# LPC55S69_MINI.net
KiCad netlist of a schematic drawn in Altium Designer
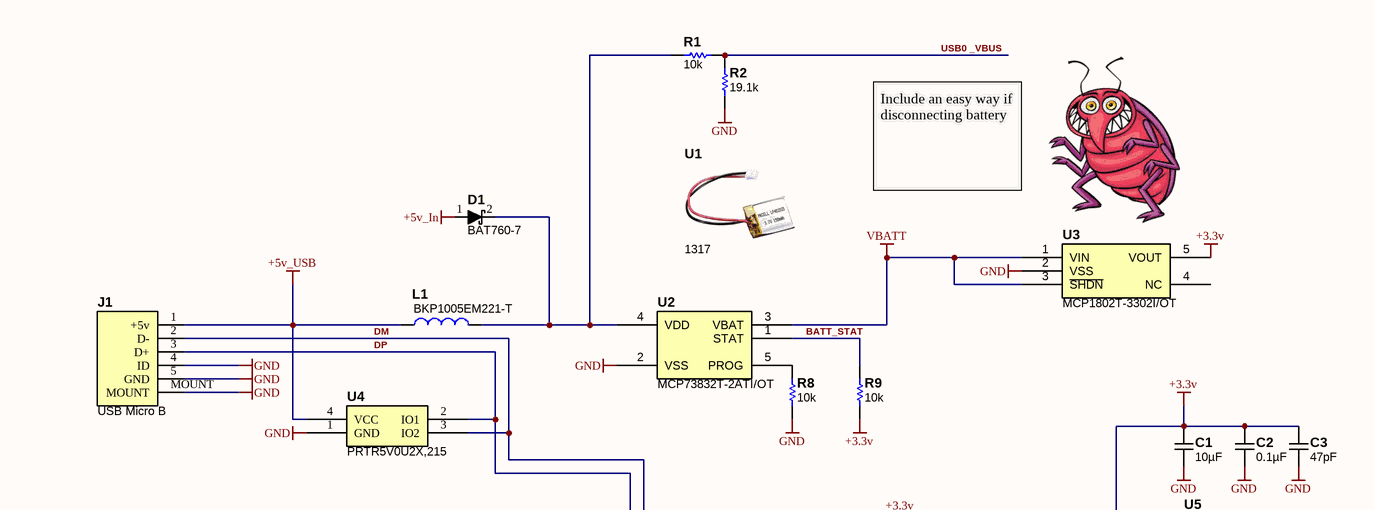
[diagram p0: LPC55S69_MINI.SchDoc, top left]
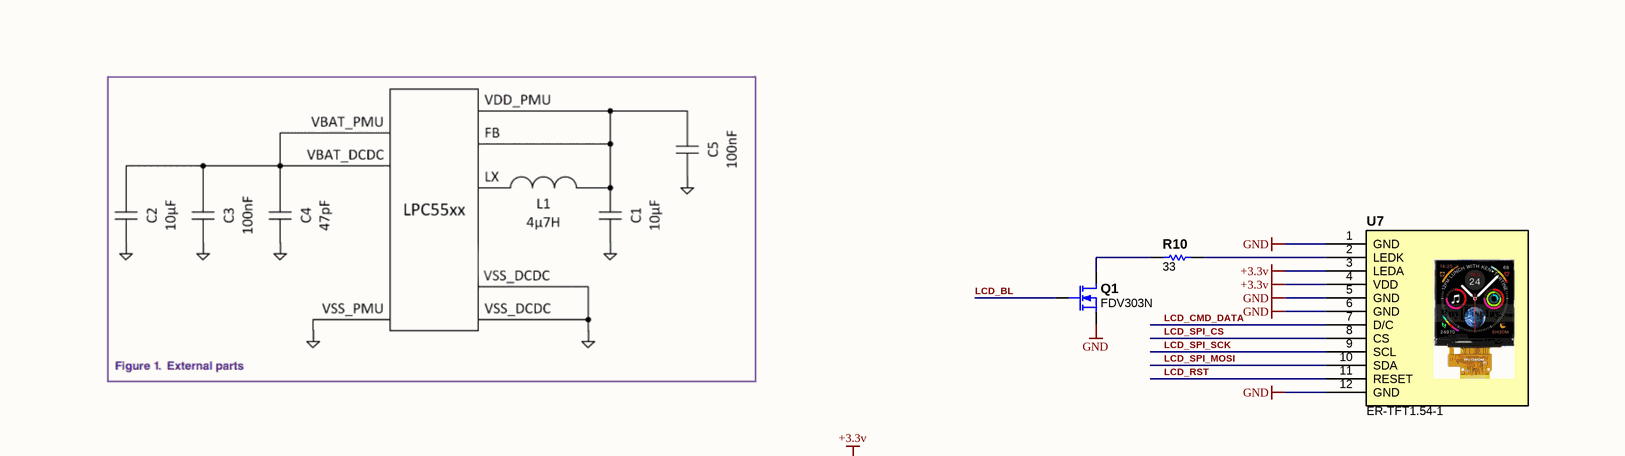
[diagram p1: LPC55S69_MINI.SchDoc, top right]
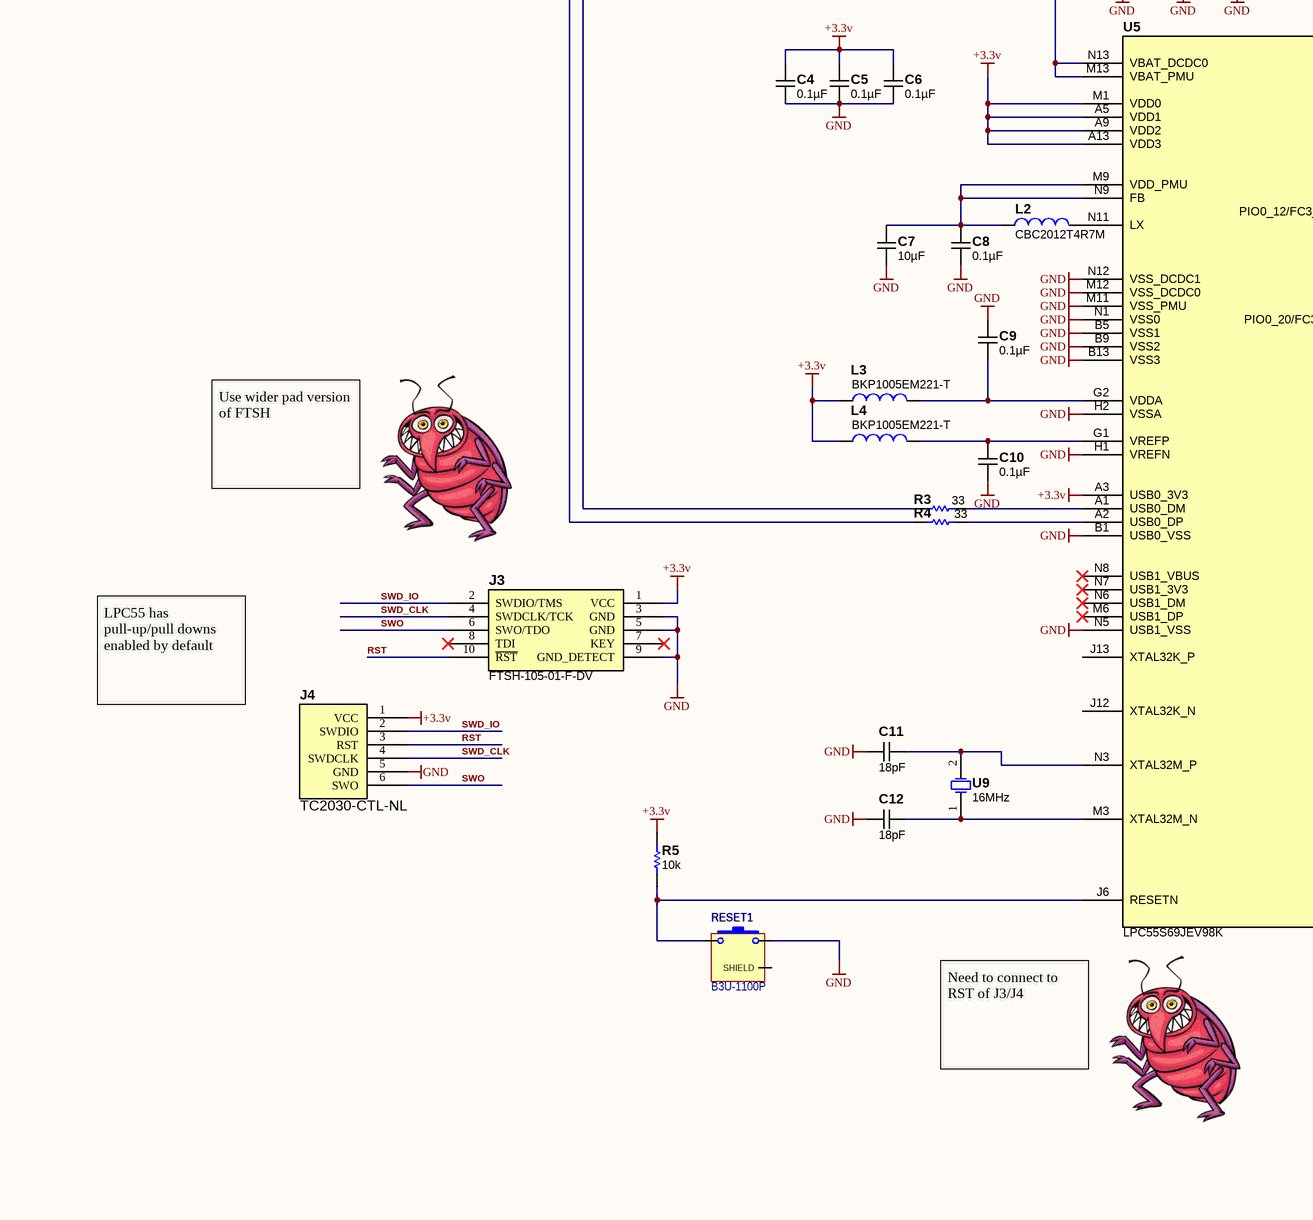
[diagram p2: LPC55S69_MINI.SchDoc, bottom left]
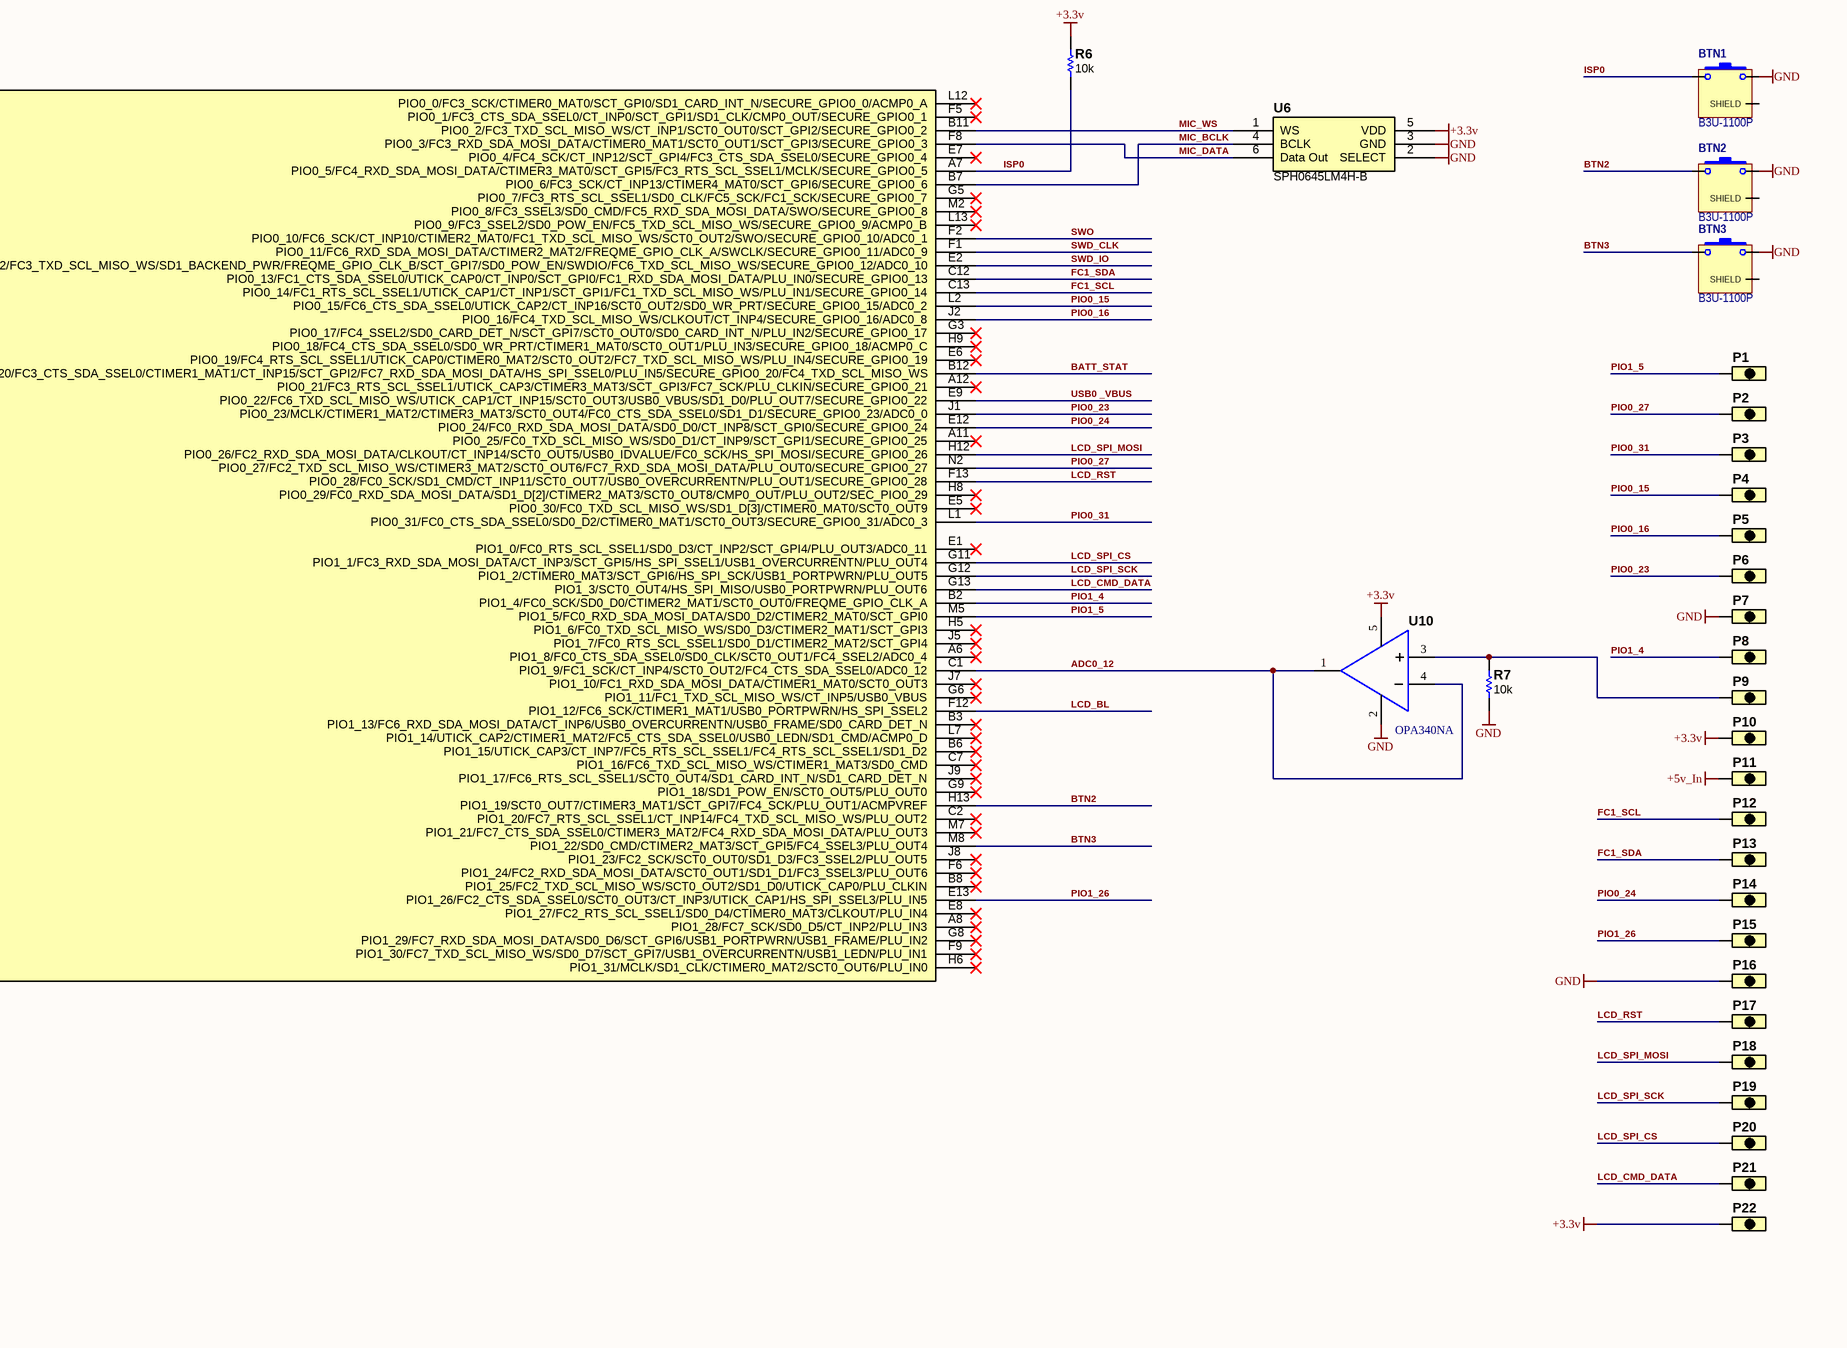
[diagram p3: LPC55S69_MINI.SchDoc, bottom right]

(export (version "E")
  (design (tool "Eeschema 10.0.6"))
  (components
    (comp (ref "BTN1")
      (value "B3U-1100P")
      (footprint "OMRON_B3U-1100P")
      (description "SWITCH TACTILE SPST-NO 0.05A 12V")
      (fields (field (name "MANUFACTURER") "Omron Electronics Inc-EMC Div"))
      (libsource (lib "Switches-N") (part "B3U-1100P"))
    )
    (comp (ref "BTN2")
      (value "B3U-1100P")
      (footprint "OMRON_B3U-1100P")
      (description "SWITCH TACTILE SPST-NO 0.05A 12V")
      (fields (field (name "MANUFACTURER") "Omron Electronics Inc-EMC Div"))
      (libsource (lib "Switches-N") (part "B3U-1100P"))
    )
    (comp (ref "BTN3")
      (value "B3U-1100P")
      (footprint "OMRON_B3U-1100P")
      (description "SWITCH TACTILE SPST-NO 0.05A 12V")
      (fields (field (name "MANUFACTURER") "Omron Electronics Inc-EMC Div"))
      (libsource (lib "Switches-N") (part "B3U-1100P"))
    )
    (comp (ref "C1")
      (value "10µF")
      (footprint "C0805_1.45MM_MD")
      (description "CAP CER 10UF 6.3V X7R 0805")
      (fields
        (field (name "MANUFACTURER PART NUMBER") "CGA4J1X7R0J106K125AC")
        (field (name "MANUFACTURER") "TDK Corporation")
      )
      (libsource (lib "Capacitors - TDK- AEC-Q200") (part "C_2P_NP"))
    )
    (comp (ref "C2")
      (value "0.1µF")
      (footprint "C0402_0.55MM_MD")
      (description "CAP CER 0.1UF 16V X7R 0402")
      (fields
        (field (name "MANUFACTURER PART NUMBER") "CGA2B1X7R1C104K050BC")
        (field (name "MANUFACTURER") "TDK Corporation")
      )
      (libsource (lib "Capacitors - TDK- AEC-Q200") (part "C_2P_NP"))
    )
    (comp (ref "C3")
      (value "47pF")
      (footprint "C0402_0.55MM_MD")
      (description "CAP CER 47PF 50V C0G 0402")
      (fields
        (field (name "MANUFACTURER PART NUMBER") "CGA2B2C0G1H470J050BA")
        (field (name "MANUFACTURER") "TDK Corporation")
      )
      (libsource (lib "Capacitors - TDK- AEC-Q200") (part "C_2P_NP"))
    )
    (comp (ref "C4")
      (value "0.1µF")
      (footprint "C0402_0.55MM_MD")
      (description "CAP CER 0.1UF 16V X7R 0402")
      (fields
        (field (name "MANUFACTURER PART NUMBER") "CGA2B1X7R1C104K050BC")
        (field (name "MANUFACTURER") "TDK Corporation")
      )
      (libsource (lib "Capacitors - TDK- AEC-Q200") (part "C_2P_NP"))
    )
    (comp (ref "C5")
      (value "0.1µF")
      (footprint "C0402_0.55MM_MD")
      (description "CAP CER 0.1UF 16V X7R 0402")
      (fields
        (field (name "MANUFACTURER PART NUMBER") "CGA2B1X7R1C104K050BC")
        (field (name "MANUFACTURER") "TDK Corporation")
      )
      (libsource (lib "Capacitors - TDK- AEC-Q200") (part "C_2P_NP"))
    )
    (comp (ref "C6")
      (value "0.1µF")
      (footprint "C0402_0.55MM_MD")
      (description "CAP CER 0.1UF 16V X7R 0402")
      (fields
        (field (name "MANUFACTURER PART NUMBER") "CGA2B1X7R1C104K050BC")
        (field (name "MANUFACTURER") "TDK Corporation")
      )
      (libsource (lib "Capacitors - TDK- AEC-Q200") (part "C_2P_NP"))
    )
    (comp (ref "C7")
      (value "10µF")
      (footprint "C0805_1.45MM_MD")
      (description "CAP CER 10UF 6.3V X7R 0805")
      (fields
        (field (name "MANUFACTURER PART NUMBER") "CGA4J1X7R0J106K125AC")
        (field (name "MANUFACTURER") "TDK Corporation")
      )
      (libsource (lib "Capacitors - TDK- AEC-Q200") (part "C_2P_NP"))
    )
    (comp (ref "C8")
      (value "0.1µF")
      (footprint "C0402_0.55MM_MD")
      (description "CAP CER 0.1UF 16V X7R 0402")
      (fields
        (field (name "MANUFACTURER PART NUMBER") "CGA2B1X7R1C104K050BC")
        (field (name "MANUFACTURER") "TDK Corporation")
      )
      (libsource (lib "Capacitors - TDK- AEC-Q200") (part "C_2P_NP"))
    )
    (comp (ref "C9")
      (value "0.1µF")
      (footprint "C0402_0.55MM_MD")
      (description "CAP CER 0.1UF 16V X7R 0402")
      (fields
        (field (name "MANUFACTURER PART NUMBER") "CGA2B1X7R1C104K050BC")
        (field (name "MANUFACTURER") "TDK Corporation")
      )
      (libsource (lib "Capacitors - TDK- AEC-Q200") (part "C_2P_NP"))
    )
    (comp (ref "C10")
      (value "0.1µF")
      (footprint "C0402_0.55MM_MD")
      (description "CAP CER 0.1UF 16V X7R 0402")
      (fields
        (field (name "MANUFACTURER PART NUMBER") "CGA2B1X7R1C104K050BC")
        (field (name "MANUFACTURER") "TDK Corporation")
      )
      (libsource (lib "Capacitors - TDK- AEC-Q200") (part "C_2P_NP"))
    )
    (comp (ref "C11")
      (value "18pF")
      (footprint "C0402_0.55MM_MD")
      (description "CAP CER 18PF 50V C0G 0402")
      (fields
        (field (name "MANUFACTURER PART NUMBER") "CGA2B2C0G1H180J050BA")
        (field (name "MANUFACTURER") "TDK Corporation")
      )
      (libsource (lib "Capacitors - TDK- AEC-Q200") (part "C_2P_NP"))
    )
    (comp (ref "C12")
      (value "18pF")
      (footprint "C0402_0.55MM_MD")
      (description "CAP CER 18PF 50V C0G 0402")
      (fields
        (field (name "MANUFACTURER PART NUMBER") "CGA2B2C0G1H180J050BA")
        (field (name "MANUFACTURER") "TDK Corporation")
      )
      (libsource (lib "Capacitors - TDK- AEC-Q200") (part "C_2P_NP"))
    )
    (comp (ref "D1")
      (value "BAT760-7")
      (footprint "D_SOD-323_P")
      (description "DIODE SCHOTTKY 30V 1A SOD323")
      (fields (field (name "MANUFACTURER") "Diodes Inc"))
      (libsource (lib "Diodes") (part "DS_1A_2C"))
    )
    (comp (ref "J1")
      (value "USB Micro B")
      (footprint "10103594-0001LF")
      (description "CONN RCPT STD MICRO USB TYPE B")
      (fields (field (name "MANUFACTURER") "FCI") (field (name "MANUFACTURER PART NUMBER") "10103594-0001LF"))
      (libsource (lib "eConnector_USB") (part "10103594-0001LF"))
    )
    (comp (ref "J3")
      (value "FTSH-105-01-F-DV")
      (footprint "FTSH-105-04-F-DV - HD - NO_STEP")
      (description "SAMTEC - FTSH-105-01-F-DV - .050 X .050")
      (fields (field (name "MANUFACTURER") "SAMTEC"))
      (libsource (lib "eConnector") (part "CORTEX-DEBUG"))
    )
    (comp (ref "J4")
      (value "TC2030‐CTL‐NL")
      (footprint "TC2030 NO LATCH")
      (description "Tag Connect Pads - No latching Clips - ARM")
      (libsource (lib "eConnector") (part "TC2030‐CTL‐NL"))
    )
    (comp (ref "L1")
      (value "BKP1005EM221-T")
      (footprint "C0402_HD")
      (description "FERRITE BEAD 220 OHM 0402 1LN")
      (fields (field (name "MANUFACTURER") "Taiyo Yuden"))
      (libsource (lib "eInductor") (part "BKP1005EM221-T"))
    )
    (comp (ref "L2")
      (value "CBC2012T4R7M")
      (footprint "C0805_1.45MM_MD")
      (description "FIXED IND 4.7UH 520MA 650 MOHM")
      (fields (field (name "MANUFACTURER") "Taiyo Yuden") (field (name "TOLERANCE") "20%"))
      (libsource (lib "eInductor") (part "CBC2012T4R7M"))
    )
    (comp (ref "L3")
      (value "BKP1005EM221-T")
      (footprint "C0402_HD")
      (description "FERRITE BEAD 220 OHM 0402 1LN")
      (fields (field (name "MANUFACTURER") "Taiyo Yuden"))
      (libsource (lib "eInductor") (part "BKP1005EM221-T"))
    )
    (comp (ref "L4")
      (value "BKP1005EM221-T")
      (footprint "C0402_HD")
      (description "FERRITE BEAD 220 OHM 0402 1LN")
      (fields (field (name "MANUFACTURER") "Taiyo Yuden"))
      (libsource (lib "eInductor") (part "BKP1005EM221-T"))
    )
    (comp (ref "P1")
      (value "~")
      (footprint "CASTELLATED")
      (libsource (lib "eConnector") (part "CASTELLATED"))
    )
    (comp (ref "P2")
      (value "~")
      (footprint "CASTELLATED")
      (libsource (lib "eConnector") (part "CASTELLATED"))
    )
    (comp (ref "P3")
      (value "~")
      (footprint "CASTELLATED")
      (libsource (lib "eConnector") (part "CASTELLATED"))
    )
    (comp (ref "P4")
      (value "~")
      (footprint "CASTELLATED")
      (libsource (lib "eConnector") (part "CASTELLATED"))
    )
    (comp (ref "P5")
      (value "~")
      (footprint "CASTELLATED")
      (libsource (lib "eConnector") (part "CASTELLATED"))
    )
    (comp (ref "P6")
      (value "~")
      (footprint "CASTELLATED")
      (libsource (lib "eConnector") (part "CASTELLATED"))
    )
    (comp (ref "P7")
      (value "~")
      (footprint "CASTELLATED")
      (libsource (lib "eConnector") (part "CASTELLATED"))
    )
    (comp (ref "P8")
      (value "~")
      (footprint "CASTELLATED")
      (libsource (lib "eConnector") (part "CASTELLATED"))
    )
    (comp (ref "P9")
      (value "~")
      (footprint "CASTELLATED")
      (libsource (lib "eConnector") (part "CASTELLATED"))
    )
    (comp (ref "P10")
      (value "~")
      (footprint "CASTELLATED")
      (libsource (lib "eConnector") (part "CASTELLATED"))
    )
    (comp (ref "P11")
      (value "~")
      (footprint "CASTELLATED")
      (libsource (lib "eConnector") (part "CASTELLATED"))
    )
    (comp (ref "P12")
      (value "~")
      (footprint "CASTELLATED")
      (libsource (lib "eConnector") (part "CASTELLATED"))
    )
    (comp (ref "P13")
      (value "~")
      (footprint "CASTELLATED")
      (libsource (lib "eConnector") (part "CASTELLATED"))
    )
    (comp (ref "P14")
      (value "~")
      (footprint "CASTELLATED")
      (libsource (lib "eConnector") (part "CASTELLATED"))
    )
    (comp (ref "P15")
      (value "~")
      (footprint "CASTELLATED")
      (libsource (lib "eConnector") (part "CASTELLATED"))
    )
    (comp (ref "P16")
      (value "~")
      (footprint "CASTELLATED")
      (libsource (lib "eConnector") (part "CASTELLATED"))
    )
    (comp (ref "P17")
      (value "~")
      (footprint "CASTELLATED")
      (libsource (lib "eConnector") (part "CASTELLATED"))
    )
    (comp (ref "P18")
      (value "~")
      (footprint "CASTELLATED")
      (libsource (lib "eConnector") (part "CASTELLATED"))
    )
    (comp (ref "P19")
      (value "~")
      (footprint "CASTELLATED")
      (libsource (lib "eConnector") (part "CASTELLATED"))
    )
    (comp (ref "P20")
      (value "~")
      (footprint "CASTELLATED")
      (libsource (lib "eConnector") (part "CASTELLATED"))
    )
    (comp (ref "P21")
      (value "~")
      (footprint "CASTELLATED")
      (libsource (lib "eConnector") (part "CASTELLATED"))
    )
    (comp (ref "P22")
      (value "~")
      (footprint "CASTELLATED")
      (libsource (lib "eConnector") (part "CASTELLATED"))
    )
    (comp (ref "Q1")
      (value "FDV303N")
      (footprint "SOT-23")
      (description "MOSFET N-CH 25V 680MA SOT-23")
      (fields (field (name "MANUFACTURER") "Fairchild Semiconductor") (field (name "SOURCE") "Digikey"))
      (libsource (lib "eTransistor") (part "FDV303N"))
    )
    (comp (ref "R1")
      (value "10k")
      (footprint "R0402_0.40MM_MD")
      (description "RES 10K OHM 1/10W 1% 0402 SMD")
      (fields
        (field (name "MANUFACTURER PART NUMBER") "ERJ-2RKF1002X")
        (field (name "MANUFACTURER") "Panasonic Electronic Components")
      )
      (libsource (lib "Resistors - Panasonic - AEC-Q200") (part "R_2P"))
    )
    (comp (ref "R2")
      (value "19.1k")
      (footprint "R0402_0.40MM_MD")
      (description "RES 19.1K OHM 1/10W 1% 0402 SMD")
      (fields
        (field (name "MANUFACTURER PART NUMBER") "ERJ-2RKF1912X")
        (field (name "MANUFACTURER") "Panasonic Electronic Components")
      )
      (libsource (lib "Resistors - Panasonic - AEC-Q200") (part "R_2P"))
    )
    (comp (ref "R3")
      (value "33")
      (footprint "R0603_0.55MM_MD")
      (description "RES 33 OHM 1/10W 1% 0603 SMD")
      (fields
        (field (name "MANUFACTURER PART NUMBER") "ERJ-3EKF33R0V")
        (field (name "MANUFACTURER") "Panasonic Electronic Components")
      )
      (libsource (lib "Resistors - Panasonic - AEC-Q200") (part "R_2P"))
    )
    (comp (ref "R4")
      (value "33")
      (footprint "R0603_0.55MM_MD")
      (description "RES 33 OHM 1/10W 1% 0603 SMD")
      (fields
        (field (name "MANUFACTURER PART NUMBER") "ERJ-3EKF33R0V")
        (field (name "MANUFACTURER") "Panasonic Electronic Components")
      )
      (libsource (lib "Resistors - Panasonic - AEC-Q200") (part "R_2P"))
    )
    (comp (ref "R5")
      (value "10k")
      (footprint "R0402_0.40MM_MD")
      (description "RES 10K OHM 1/10W 1% 0402 SMD")
      (fields
        (field (name "MANUFACTURER PART NUMBER") "ERJ-2RKF1002X")
        (field (name "MANUFACTURER") "Panasonic Electronic Components")
      )
      (libsource (lib "Resistors - Panasonic - AEC-Q200") (part "R_2P"))
    )
    (comp (ref "R6")
      (value "10k")
      (footprint "R0402_0.40MM_MD")
      (description "RES 10K OHM 1/10W 1% 0402 SMD")
      (fields
        (field (name "MANUFACTURER PART NUMBER") "ERJ-2RKF1002X")
        (field (name "MANUFACTURER") "Panasonic Electronic Components")
      )
      (libsource (lib "Resistors - Panasonic - AEC-Q200") (part "R_2P"))
    )
    (comp (ref "R7")
      (value "10k")
      (footprint "R0402_0.40MM_MD")
      (description "RES 10K OHM 1/10W 1% 0402 SMD")
      (fields
        (field (name "MANUFACTURER PART NUMBER") "ERJ-2RKF1002X")
        (field (name "MANUFACTURER") "Panasonic Electronic Components")
      )
      (libsource (lib "Resistors - Panasonic - AEC-Q200") (part "R_2P"))
    )
    (comp (ref "R8")
      (value "10k")
      (footprint "R0402_0.40MM_MD")
      (description "RES 10K OHM 1/10W 1% 0402 SMD")
      (fields
        (field (name "MANUFACTURER PART NUMBER") "ERJ-2RKF1002X")
        (field (name "MANUFACTURER") "Panasonic Electronic Components")
      )
      (libsource (lib "Resistors - Panasonic - AEC-Q200") (part "R_2P"))
    )
    (comp (ref "R9")
      (value "10k")
      (footprint "R0402_0.40MM_MD")
      (description "RES 10K OHM 1/10W 1% 0402 SMD")
      (fields
        (field (name "MANUFACTURER PART NUMBER") "ERJ-2RKF1002X")
        (field (name "MANUFACTURER") "Panasonic Electronic Components")
      )
      (libsource (lib "Resistors - Panasonic - AEC-Q200") (part "R_2P"))
    )
    (comp (ref "R10")
      (value "33")
      (footprint "R0603_0.55MM_MD")
      (description "RES 33 OHM 1/10W 1% 0603 SMD")
      (fields
        (field (name "MANUFACTURER PART NUMBER") "ERJ-3EKF33R0V")
        (field (name "MANUFACTURER") "Panasonic Electronic Components")
      )
      (libsource (lib "Resistors - Panasonic - AEC-Q200") (part "R_2P"))
    )
    (comp (ref "RESET1")
      (value "B3U-1100P")
      (footprint "OMRON_B3U-1100P")
      (description "SWITCH TACTILE SPST-NO 0.05A 12V")
      (fields (field (name "MANUFACTURER") "Omron Electronics Inc-EMC Div"))
      (libsource (lib "Switches-N") (part "B3U-1100P"))
    )
    (comp (ref "U1")
      (value "1317")
      (footprint "LIPO-150MAH")
      (description "FLORA LI-PO BATTERY 3.7V 150MAH")
      (fields (field (name "MANUFACTURER") "Adafruit Industries"))
      (libsource (lib "eBattery") (part "1317"))
    )
    (comp (ref "U2")
      (value "MCP73832T-2ATI/OT")
      (footprint "SOT23-5")
      (description "Charge Controller Li-Ion/Li-Pol 15mA to 500mA 4.2V 5-Pin SOT-23 T/R")
      (fields (field (name "MANUFACTURER") "Microchip"))
      (libsource (lib "eIC") (part "MCP73832T-2ATI/OT"))
    )
    (comp (ref "U3")
      (value "MCP1802T-3302I/OT")
      (footprint "SOT23-5")
      (description "IC REG LINEAR 3.3V 300MA SOT23-5")
      (fields (field (name "MANUFACTURER") "Microchip"))
      (libsource (lib "eIC_Regulator") (part "MCP1802T-3302I/OT"))
    )
    (comp (ref "U4")
      (value "PRTR5V0U2X,215")
      (footprint "SOT143B")
      (description "TVS DIODE 5.5VWM SOT143B")
      (fields (field (name "MANUFACTURER") "NXP Semiconductors"))
      (libsource (lib "eDiode") (part "PRTR5V0U2X,215"))
    )
    (comp (ref "U5")
      (value "LPC55S69JEV98K")
      (footprint "98-VFBGA")
      (description "IC MCU 100MHZ CORTEX M33 DUAL")
      (fields (field (name "MANUFACTURER") "NXP Semiconductors"))
      (libsource (lib "eIC") (part "LPC55S69JEV98K"))
    )
    (comp (ref "U6")
      (value "SPH0645LM4H-B")
      (footprint "SPH0645LM4H-B")
      (fields (field (name "MANUFACTURER") "Knowles Acoustics"))
      (libsource (lib "eAudio") (part "SPH0645LM4H-B"))
    )
    (comp (ref "U7")
      (value "ER-TFT1.54-1")
      (footprint "ER-TFT1.54-1")
      (description "1.54\" 240x240 IPS Display")
      (fields (field (name "MANUFACTURER") "Buy Display"))
      (libsource (lib "eDisplay") (part "ER-TFT1.54-1"))
    )
    (comp (ref "U9")
      (value "16MHz")
      (footprint "ABM3")
      (description "Crystal 16MHz ±20ppm (Tol) ±50ppm (Stability) 18pF FUND 50Ohm 2-Pin CSMD T/R")
      (fields
        (field (name "MANUFACTURER") "Abracon")
        (field (name "MANUFACTURER PART NUMBER") "ABM3-16.000MHZ-B2-T")
      )
      (libsource (lib "eCrystal") (part "ABM3-16.000MHZ-B2-T"))
    )
    (comp (ref "U10")
      (value "OPA340NA")
      (footprint "SOT95P245X145-5L")
      (description "IC SINGLE SUPPLY OPAMP SOT-23-5")
      (fields
        (field (name "MANUFACTURER") "Texas Instruments")
        (field (name "MANUFACTURER PART NUMBER") "OPA340NA/250")
        (field (name "SOURCE") "Digikey")
      )
      (libsource (lib "eOPAMP") (part "OPA340"))
    )
  )
  (nets
    (net (code "1") (name "+3.3v") (class "Default")
      (node (ref "C1") (pin "2") (pinfunction "1_2") (pintype "passive"))
      (node (ref "C2") (pin "2") (pinfunction "1_2") (pintype "passive"))
      (node (ref "C3") (pin "2") (pinfunction "1_2") (pintype "passive"))
      (node (ref "C4") (pin "2") (pinfunction "1_2") (pintype "passive"))
      (node (ref "C5") (pin "2") (pinfunction "1_2") (pintype "passive"))
      (node (ref "C6") (pin "2") (pinfunction "1_2") (pintype "passive"))
      (node (ref "J3") (pin "1") (pinfunction "VCC_1") (pintype "passive"))
      (node (ref "J4") (pin "1") (pinfunction "VCC_1") (pintype "passive"))
      (node (ref "L3") (pin "1") (pinfunction "1_1") (pintype "passive"))
      (node (ref "L4") (pin "1") (pinfunction "1_1") (pintype "passive"))
      (node (ref "P10") (pin "1") (pinfunction "1_1") (pintype "passive"))
      (node (ref "P22") (pin "1") (pinfunction "1_1") (pintype "passive"))
      (node (ref "R5") (pin "2") (pinfunction "2_2") (pintype "passive"))
      (node (ref "R6") (pin "2") (pinfunction "2_2") (pintype "passive"))
      (node (ref "R9") (pin "1") (pinfunction "1_1") (pintype "passive"))
      (node (ref "U10") (pin "5") (pinfunction "VCC_5") (pintype "passive"))
      (node (ref "U3") (pin "5") (pinfunction "VOUT_5") (pintype "passive"))
      (node (ref "U5") (pin "A13") (pinfunction "VDD3_A13") (pintype "passive"))
      (node (ref "U5") (pin "A3") (pinfunction "USB0_3V3_A3") (pintype "passive"))
      (node (ref "U5") (pin "A5") (pinfunction "VDD1_A5") (pintype "passive"))
      (node (ref "U5") (pin "A9") (pinfunction "VDD2_A9") (pintype "passive"))
      (node (ref "U5") (pin "M1") (pinfunction "VDD0_M1") (pintype "passive"))
      (node (ref "U5") (pin "M13") (pinfunction "VBAT_PMU_M13") (pintype "passive"))
      (node (ref "U5") (pin "N13") (pinfunction "VBAT_DCDC0_N13") (pintype "passive"))
      (node (ref "U6") (pin "5") (pinfunction "VDD_5") (pintype "passive"))
      (node (ref "U7") (pin "3") (pinfunction "LEDA_3") (pintype "passive"))
      (node (ref "U7") (pin "4") (pinfunction "VDD_4") (pintype "passive"))
    )
    (net (code "2") (name "+5v_In") (class "Default")
      (node (ref "D1") (pin "1") (pinfunction "A_1") (pintype "passive"))
      (node (ref "P11") (pin "1") (pinfunction "1_1") (pintype "passive"))
    )
    (net (code "3") (name "+5v_USB") (class "Default")
      (node (ref "J1") (pin "1") (pinfunction "+5v_1") (pintype "passive"))
      (node (ref "L1") (pin "1") (pinfunction "1_1") (pintype "passive"))
      (node (ref "U4") (pin "4") (pinfunction "VCC_4") (pintype "passive"))
    )
    (net (code "4") (name "/ADC0_12") (class "Default")
      (node (ref "U10") (pin "1") (pinfunction "OUT_1") (pintype "passive"))
      (node (ref "U10") (pin "4") (pinfunction "-_4") (pintype "passive"))
      (node (ref "U5") (pin "C1") (pinfunction "PIO1_9/FC1_SCK/CT_INP4/SCT0_OUT2/FC4_CTS_SDA_SSEL0/ADC0_12_C1") (pintype "passive"))
    )
    (net (code "5") (name "/BATT_STAT") (class "Default")
      (node (ref "R9") (pin "2") (pinfunction "2_2") (pintype "passive"))
      (node (ref "U2") (pin "1") (pinfunction "STAT_1") (pintype "passive"))
      (node (ref "U5") (pin "B12") (pinfunction "PIO0_20/FC3_CTS_SDA_SSEL0/CTIMER1_MAT1/CT_INP15/SCT_GPI2/FC7_RXD_SDA_MOSI_DATA/HS_SPI_SSEL0/PLU_IN5/SECURE_GPIO0_20/FC4_TXD_SCL_MISO_WS_B12") (pintype "passive"))
    )
    (net (code "6") (name "/BTN2") (class "Default")
      (node (ref "BTN2") (pin "2") (pinfunction "2_2") (pintype "passive"))
      (node (ref "U5") (pin "H13") (pinfunction "PIO1_19/SCT0_OUT7/CTIMER3_MAT1/SCT_GPI7/FC4_SCK/PLU_OUT1/ACMPVREF_H13") (pintype "passive"))
    )
    (net (code "7") (name "/BTN3") (class "Default")
      (node (ref "BTN3") (pin "2") (pinfunction "2_2") (pintype "passive"))
      (node (ref "U5") (pin "M8") (pinfunction "PIO1_22/SD0_CMD/CTIMER2_MAT3/SCT_GPI5/FC4_SSEL3/PLU_OUT4_M8") (pintype "passive"))
    )
    (net (code "8") (name "/DM") (class "Default")
      (node (ref "J1") (pin "2") (pinfunction "D-_2") (pintype "passive"))
      (node (ref "R3") (pin "1") (pinfunction "1_1") (pintype "passive"))
      (node (ref "U4") (pin "3") (pinfunction "IO2_3") (pintype "passive"))
    )
    (net (code "9") (name "/DP") (class "Default")
      (node (ref "J1") (pin "3") (pinfunction "D+_3") (pintype "passive"))
      (node (ref "R4") (pin "1") (pinfunction "1_1") (pintype "passive"))
      (node (ref "U4") (pin "2") (pinfunction "IO1_2") (pintype "passive"))
    )
    (net (code "10") (name "/FC1_SCL") (class "Default")
      (node (ref "P12") (pin "1") (pinfunction "1_1") (pintype "passive"))
      (node (ref "U5") (pin "C13") (pinfunction "PIO0_14/FC1_RTS_SCL_SSEL1/UTICK_CAP1/CT_INP1/SCT_GPI1/FC1_TXD_SCL_MISO_WS/PLU_IN1/SECURE_GPIO0_14_C13") (pintype "passive"))
    )
    (net (code "11") (name "/FC1_SDA") (class "Default")
      (node (ref "P13") (pin "1") (pinfunction "1_1") (pintype "passive"))
      (node (ref "U5") (pin "C12") (pinfunction "PIO0_13/FC1_CTS_SDA_SSEL0/UTICK_CAP0/CT_INP0/SCT_GPI0/FC1_RXD_SDA_MOSI_DATA/PLU_IN0/SECURE_GPIO0_13_C12") (pintype "passive"))
    )
    (net (code "12") (name "/ISP0") (class "Default")
      (node (ref "BTN1") (pin "2") (pinfunction "2_2") (pintype "passive"))
      (node (ref "R6") (pin "1") (pinfunction "1_1") (pintype "passive"))
      (node (ref "U5") (pin "A7") (pinfunction "PIO0_5/FC4_RXD_SDA_MOSI_DATA/CTIMER3_MAT0/SCT_GPI5/FC3_RTS_SCL_SSEL1/MCLK/SECURE_GPIO0_5_A7") (pintype "passive"))
    )
    (net (code "13") (name "/LCD_BL") (class "Default")
      (node (ref "Q1") (pin "1") (pinfunction "G_1") (pintype "passive"))
      (node (ref "U5") (pin "F12") (pinfunction "PIO1_12/FC6_SCK/CTIMER1_MAT1/USB0_PORTPWRN/HS_SPI_SSEL2_F12") (pintype "passive"))
    )
    (net (code "14") (name "/LCD_CMD_DATA") (class "Default")
      (node (ref "P21") (pin "1") (pinfunction "1_1") (pintype "passive"))
      (node (ref "U5") (pin "G13") (pinfunction "PIO1_3/SCT0_OUT4/HS_SPI_MISO/USB0_PORTPWRN/PLU_OUT6_G13") (pintype "passive"))
      (node (ref "U7") (pin "7") (pinfunction "D/C_7") (pintype "passive"))
    )
    (net (code "15") (name "/LCD_RST") (class "Default")
      (node (ref "P17") (pin "1") (pinfunction "1_1") (pintype "passive"))
      (node (ref "U5") (pin "F13") (pinfunction "PIO0_28/FC0_SCK/SD1_CMD/CT_INP11/SCT0_OUT7/USB0_OVERCURRENTN/PLU_OUT1/SECURE_GPIO0_28_F13") (pintype "passive"))
      (node (ref "U7") (pin "11") (pinfunction "RESET_11") (pintype "passive"))
    )
    (net (code "16") (name "/LCD_SPI_CS") (class "Default")
      (node (ref "P20") (pin "1") (pinfunction "1_1") (pintype "passive"))
      (node (ref "U5") (pin "G11") (pinfunction "PIO1_1/FC3_RXD_SDA_MOSI_DATA/CT_INP3/SCT_GPI5/HS_SPI_SSEL1/USB1_OVERCURRENTN/PLU_OUT4_G11") (pintype "passive"))
      (node (ref "U7") (pin "8") (pinfunction "CS_8") (pintype "passive"))
    )
    (net (code "17") (name "/LCD_SPI_MOSI") (class "Default")
      (node (ref "P18") (pin "1") (pinfunction "1_1") (pintype "passive"))
      (node (ref "U5") (pin "H12") (pinfunction "PIO0_26/FC2_RXD_SDA_MOSI_DATA/CLKOUT/CT_INP14/SCT0_OUT5/USB0_IDVALUE/FC0_SCK/HS_SPI_MOSI/SECURE_GPIO0_26_H12") (pintype "passive"))
      (node (ref "U7") (pin "10") (pinfunction "SDA_10") (pintype "passive"))
    )
    (net (code "18") (name "/LCD_SPI_SCK") (class "Default")
      (node (ref "P19") (pin "1") (pinfunction "1_1") (pintype "passive"))
      (node (ref "U5") (pin "G12") (pinfunction "PIO1_2/CTIMER0_MAT3/SCT_GPI6/HS_SPI_SCK/USB1_PORTPWRN/PLU_OUT5_G12") (pintype "passive"))
      (node (ref "U7") (pin "9") (pinfunction "SCL_9") (pintype "passive"))
    )
    (net (code "19") (name "/MIC_BCLK") (class "Default")
      (node (ref "U5") (pin "B7") (pinfunction "PIO0_6/FC3_SCK/CT_INP13/CTIMER4_MAT0/SCT_GPI6/SECURE_GPIO0_6_B7") (pintype "passive"))
      (node (ref "U6") (pin "4") (pinfunction "BCLK_4") (pintype "passive"))
    )
    (net (code "20") (name "/MIC_DATA") (class "Default")
      (node (ref "U5") (pin "F8") (pinfunction "PIO0_3/FC3_RXD_SDA_MOSI_DATA/CTIMER0_MAT1/SCT0_OUT1/SCT_GPI3/SECURE_GPIO0_3_F8") (pintype "passive"))
      (node (ref "U6") (pin "6") (pinfunction "Data_Out_6") (pintype "passive"))
    )
    (net (code "21") (name "/MIC_WS") (class "Default")
      (node (ref "U5") (pin "B11") (pinfunction "PIO0_2/FC3_TXD_SCL_MISO_WS/CT_INP1/SCT0_OUT0/SCT_GPI2/SECURE_GPIO0_2_B11") (pintype "passive"))
      (node (ref "U6") (pin "1") (pinfunction "WS_1") (pintype "passive"))
    )
    (net (code "22") (name "/PIO0_15") (class "Default")
      (node (ref "P4") (pin "1") (pinfunction "1_1") (pintype "passive"))
      (node (ref "U5") (pin "L2") (pinfunction "PIO0_15/FC6_CTS_SDA_SSEL0/UTICK_CAP2/CT_INP16/SCT0_OUT2/SD0_WR_PRT/SECURE_GPIO0_15/ADC0_2_L2") (pintype "passive"))
    )
    (net (code "23") (name "/PIO0_16") (class "Default")
      (node (ref "P5") (pin "1") (pinfunction "1_1") (pintype "passive"))
      (node (ref "U5") (pin "J2") (pinfunction "PIO0_16/FC4_TXD_SCL_MISO_WS/CLKOUT/CT_INP4/SECURE_GPIO0_16/ADC0_8_J2") (pintype "passive"))
    )
    (net (code "24") (name "/PIO0_23") (class "Default")
      (node (ref "P6") (pin "1") (pinfunction "1_1") (pintype "passive"))
      (node (ref "U5") (pin "J1") (pinfunction "PIO0_23/MCLK/CTIMER1_MAT2/CTIMER3_MAT3/SCT0_OUT4/FC0_CTS_SDA_SSEL0/SD1_D1/SECURE_GPIO0_23/ADC0_0_J1") (pintype "passive"))
    )
    (net (code "25") (name "/PIO0_24") (class "Default")
      (node (ref "P14") (pin "1") (pinfunction "1_1") (pintype "passive"))
      (node (ref "U5") (pin "E12") (pinfunction "PIO0_24/FC0_RXD_SDA_MOSI_DATA/SD0_D0/CT_INP8/SCT_GPI0/SECURE_GPIO0_24_E12") (pintype "passive"))
    )
    (net (code "26") (name "/PIO0_27") (class "Default")
      (node (ref "P2") (pin "1") (pinfunction "1_1") (pintype "passive"))
      (node (ref "U5") (pin "N2") (pinfunction "PIO0_27/FC2_TXD_SCL_MISO_WS/CTIMER3_MAT2/SCT0_OUT6/FC7_RXD_SDA_MOSI_DATA/PLU_OUT0/SECURE_GPIO0_27_N2") (pintype "passive"))
    )
    (net (code "27") (name "/PIO0_31") (class "Default")
      (node (ref "P3") (pin "1") (pinfunction "1_1") (pintype "passive"))
      (node (ref "U5") (pin "L1") (pinfunction "PIO0_31/FC0_CTS_SDA_SSEL0/SD0_D2/CTIMER0_MAT1/SCT0_OUT3/SECURE_GPIO0_31/ADC0_3_L1") (pintype "passive"))
    )
    (net (code "28") (name "/PIO1_4") (class "Default")
      (node (ref "P8") (pin "1") (pinfunction "1_1") (pintype "passive"))
      (node (ref "U5") (pin "B2") (pinfunction "PIO1_4/FC0_SCK/SD0_D0/CTIMER2_MAT1/SCT0_OUT0/FREQME_GPIO_CLK_A_B2") (pintype "passive"))
    )
    (net (code "29") (name "/PIO1_5") (class "Default")
      (node (ref "P1") (pin "1") (pinfunction "1_1") (pintype "passive"))
      (node (ref "U5") (pin "M5") (pinfunction "PIO1_5/FC0_RXD_SDA_MOSI_DATA/SD0_D2/CTIMER2_MAT0/SCT_GPI0_M5") (pintype "passive"))
    )
    (net (code "30") (name "/PIO1_26") (class "Default")
      (node (ref "P15") (pin "1") (pinfunction "1_1") (pintype "passive"))
      (node (ref "U5") (pin "E13") (pinfunction "PIO1_26/FC2_CTS_SDA_SSEL0/SCT0_OUT3/CT_INP3/UTICK_CAP1/HS_SPI_SSEL3/PLU_IN5_E13") (pintype "passive"))
    )
    (net (code "31") (name "/RST") (class "Default")
      (node (ref "J3") (pin "10") (pinfunction "~{RST}_10") (pintype "passive"))
      (node (ref "J4") (pin "3") (pinfunction "RST_3") (pintype "passive"))
    )
    (net (code "32") (name "/SWD_CLK") (class "Default")
      (node (ref "J3") (pin "4") (pinfunction "SWDCLK/TCK_4") (pintype "passive"))
      (node (ref "J4") (pin "4") (pinfunction "SWDCLK_4") (pintype "passive"))
      (node (ref "U5") (pin "F1") (pinfunction "PIO0_11/FC6_RXD_SDA_MOSI_DATA/CTIMER2_MAT2/FREQME_GPIO_CLK_A/SWCLK/SECURE_GPIO0_11/ADC0_9_F1") (pintype "passive"))
    )
    (net (code "33") (name "/SWD_IO") (class "Default")
      (node (ref "J3") (pin "2") (pinfunction "SWDIO/TMS_2") (pintype "passive"))
      (node (ref "J4") (pin "2") (pinfunction "SWDIO_2") (pintype "passive"))
      (node (ref "U5") (pin "E2") (pinfunction "PIO0_12/FC3_TXD_SCL_MISO_WS/SD1_BACKEND_PWR/FREQME_GPIO_CLK_B/SCT_GPI7/SD0_POW_EN/SWDIO/FC6_TXD_SCL_MISO_WS/SECURE_GPIO0_12/ADC0_10_E2") (pintype "passive"))
    )
    (net (code "34") (name "/SWO") (class "Default")
      (node (ref "J3") (pin "6") (pinfunction "SWO/TDO_6") (pintype "passive"))
      (node (ref "J4") (pin "6") (pinfunction "SWO_6") (pintype "passive"))
      (node (ref "U5") (pin "F2") (pinfunction "PIO0_10/FC6_SCK/CT_INP10/CTIMER2_MAT0/FC1_TXD_SCL_MISO_WS/SCT0_OUT2/SWO/SECURE_GPIO0_10/ADC0_1_F2") (pintype "passive"))
    )
    (net (code "35") (name "/USB0 _VBUS") (class "Default")
      (node (ref "R1") (pin "2") (pinfunction "2_2") (pintype "passive"))
      (node (ref "R2") (pin "2") (pinfunction "2_2") (pintype "passive"))
      (node (ref "U5") (pin "E9") (pinfunction "PIO0_22/FC6_TXD_SCL_MISO_WS/UTICK_CAP1/CT_INP15/SCT0_OUT3/USB0_VBUS/SD1_D0/PLU_OUT7/SECURE_GPIO0_22_E9") (pintype "passive"))
    )
    (net (code "36") (name "GND") (class "Default")
      (node (ref "BTN1") (pin "1") (pinfunction "1_1") (pintype "passive"))
      (node (ref "BTN2") (pin "1") (pinfunction "1_1") (pintype "passive"))
      (node (ref "BTN3") (pin "1") (pinfunction "1_1") (pintype "passive"))
      (node (ref "C1") (pin "1") (pinfunction "1_1") (pintype "passive"))
      (node (ref "C10") (pin "1") (pinfunction "1_1") (pintype "passive"))
      (node (ref "C11") (pin "1") (pinfunction "1_1") (pintype "passive"))
      (node (ref "C12") (pin "1") (pinfunction "1_1") (pintype "passive"))
      (node (ref "C2") (pin "1") (pinfunction "1_1") (pintype "passive"))
      (node (ref "C3") (pin "1") (pinfunction "1_1") (pintype "passive"))
      (node (ref "C4") (pin "1") (pinfunction "1_1") (pintype "passive"))
      (node (ref "C5") (pin "1") (pinfunction "1_1") (pintype "passive"))
      (node (ref "C6") (pin "1") (pinfunction "1_1") (pintype "passive"))
      (node (ref "C7") (pin "1") (pinfunction "1_1") (pintype "passive"))
      (node (ref "C8") (pin "1") (pinfunction "1_1") (pintype "passive"))
      (node (ref "C9") (pin "2") (pinfunction "1_2") (pintype "passive"))
      (node (ref "J1") (pin "4") (pinfunction "ID_4") (pintype "passive"))
      (node (ref "J1") (pin "5") (pinfunction "GND_5") (pintype "passive"))
      (node (ref "J1") (pin "MOUNT") (pinfunction "MOUNT_MOUNT") (pintype "passive"))
      (node (ref "J3") (pin "3") (pinfunction "GND_3") (pintype "passive"))
      (node (ref "J3") (pin "5") (pinfunction "GND_5") (pintype "passive"))
      (node (ref "J3") (pin "9") (pinfunction "GND_DETECT_9") (pintype "passive"))
      (node (ref "J4") (pin "5") (pinfunction "GND_5") (pintype "passive"))
      (node (ref "P16") (pin "1") (pinfunction "1_1") (pintype "passive"))
      (node (ref "P7") (pin "1") (pinfunction "1_1") (pintype "passive"))
      (node (ref "Q1") (pin "2") (pinfunction "S_2") (pintype "passive"))
      (node (ref "R2") (pin "1") (pinfunction "1_1") (pintype "passive"))
      (node (ref "R7") (pin "1") (pinfunction "1_1") (pintype "passive"))
      (node (ref "R8") (pin "1") (pinfunction "1_1") (pintype "passive"))
      (node (ref "RESET1") (pin "1") (pinfunction "1_1") (pintype "passive"))
      (node (ref "U10") (pin "2") (pinfunction "GND_2") (pintype "passive"))
      (node (ref "U2") (pin "2") (pinfunction "VSS_2") (pintype "passive"))
      (node (ref "U3") (pin "2") (pinfunction "VSS_2") (pintype "passive"))
      (node (ref "U4") (pin "1") (pinfunction "GND_1") (pintype "passive"))
      (node (ref "U5") (pin "B1") (pinfunction "USB0_VSS_B1") (pintype "passive"))
      (node (ref "U5") (pin "B13") (pinfunction "VSS3_B13") (pintype "passive"))
      (node (ref "U5") (pin "B5") (pinfunction "VSS1_B5") (pintype "passive"))
      (node (ref "U5") (pin "B9") (pinfunction "VSS2_B9") (pintype "passive"))
      (node (ref "U5") (pin "H1") (pinfunction "VREFN_H1") (pintype "passive"))
      (node (ref "U5") (pin "H2") (pinfunction "VSSA_H2") (pintype "passive"))
      (node (ref "U5") (pin "M11") (pinfunction "VSS_PMU_M11") (pintype "passive"))
      (node (ref "U5") (pin "M12") (pinfunction "VSS_DCDC0_M12") (pintype "passive"))
      (node (ref "U5") (pin "N1") (pinfunction "VSS0_N1") (pintype "passive"))
      (node (ref "U5") (pin "N12") (pinfunction "VSS_DCDC1_N12") (pintype "passive"))
      (node (ref "U5") (pin "N5") (pinfunction "USB1_VSS_N5") (pintype "passive"))
      (node (ref "U6") (pin "2") (pinfunction "SELECT_2") (pintype "passive"))
      (node (ref "U6") (pin "3") (pinfunction "GND_3") (pintype "passive"))
      (node (ref "U7") (pin "1") (pinfunction "GND_1") (pintype "passive"))
      (node (ref "U7") (pin "12") (pinfunction "GND_12") (pintype "passive"))
      (node (ref "U7") (pin "5") (pinfunction "GND_5") (pintype "passive"))
      (node (ref "U7") (pin "6") (pinfunction "GND_6") (pintype "passive"))
    )
    (net (code "37") (name "Net-(D1-K)") (class "Default")
      (node (ref "D1") (pin "2") (pinfunction "K_2") (pintype "passive"))
      (node (ref "L1") (pin "2") (pinfunction "2_2") (pintype "passive"))
      (node (ref "R1") (pin "1") (pinfunction "1_1") (pintype "passive"))
      (node (ref "U2") (pin "4") (pinfunction "VDD_4") (pintype "passive"))
    )
    (net (code "38") (name "Net-(Q1-D)") (class "Default")
      (node (ref "Q1") (pin "3") (pinfunction "D_3") (pintype "passive"))
      (node (ref "R10") (pin "1") (pinfunction "1_1") (pintype "passive"))
    )
    (net (code "39") (name "Net-(U2-PROG)") (class "Default")
      (node (ref "R8") (pin "2") (pinfunction "2_2") (pintype "passive"))
      (node (ref "U2") (pin "5") (pinfunction "PROG_5") (pintype "passive"))
    )
    (net (code "40") (name "Net-(U5-FB)") (class "Default")
      (node (ref "C7") (pin "2") (pinfunction "1_2") (pintype "passive"))
      (node (ref "C8") (pin "2") (pinfunction "1_2") (pintype "passive"))
      (node (ref "L2") (pin "1") (pinfunction "1_1") (pintype "passive"))
      (node (ref "U5") (pin "M9") (pinfunction "VDD_PMU_M9") (pintype "passive"))
      (node (ref "U5") (pin "N9") (pinfunction "FB_N9") (pintype "passive"))
    )
    (net (code "41") (name "Net-(U5-LX)") (class "Default")
      (node (ref "L2") (pin "2") (pinfunction "2_2") (pintype "passive"))
      (node (ref "U5") (pin "N11") (pinfunction "LX_N11") (pintype "passive"))
    )
    (net (code "42") (name "Net-(U5-RESETN)") (class "Default")
      (node (ref "R5") (pin "1") (pinfunction "1_1") (pintype "passive"))
      (node (ref "RESET1") (pin "2") (pinfunction "2_2") (pintype "passive"))
      (node (ref "U5") (pin "J6") (pinfunction "RESETN_J6") (pintype "passive"))
    )
    (net (code "43") (name "Net-(U5-USB0_DM)") (class "Default")
      (node (ref "R3") (pin "2") (pinfunction "2_2") (pintype "passive"))
      (node (ref "U5") (pin "A1") (pinfunction "USB0_DM_A1") (pintype "passive"))
    )
    (net (code "44") (name "Net-(U5-USB0_DP)") (class "Default")
      (node (ref "R4") (pin "2") (pinfunction "2_2") (pintype "passive"))
      (node (ref "U5") (pin "A2") (pinfunction "USB0_DP_A2") (pintype "passive"))
    )
    (net (code "45") (name "Net-(U5-VDDA)") (class "Default")
      (node (ref "C9") (pin "1") (pinfunction "1_1") (pintype "passive"))
      (node (ref "L3") (pin "2") (pinfunction "2_2") (pintype "passive"))
      (node (ref "U5") (pin "G2") (pinfunction "VDDA_G2") (pintype "passive"))
    )
    (net (code "46") (name "Net-(U5-VREFP)") (class "Default")
      (node (ref "C10") (pin "2") (pinfunction "1_2") (pintype "passive"))
      (node (ref "L4") (pin "2") (pinfunction "2_2") (pintype "passive"))
      (node (ref "U5") (pin "G1") (pinfunction "VREFP_G1") (pintype "passive"))
    )
    (net (code "47") (name "Net-(U5-XTAL32M_N)") (class "Default")
      (node (ref "C12") (pin "2") (pinfunction "1_2") (pintype "passive"))
      (node (ref "U5") (pin "M3") (pinfunction "XTAL32M_N_M3") (pintype "passive"))
      (node (ref "U9") (pin "1") (pinfunction "OSC1_1") (pintype "passive"))
    )
    (net (code "48") (name "Net-(U5-XTAL32M_P)") (class "Default")
      (node (ref "C11") (pin "2") (pinfunction "1_2") (pintype "passive"))
      (node (ref "U5") (pin "N3") (pinfunction "XTAL32M_P_N3") (pintype "passive"))
      (node (ref "U9") (pin "2") (pinfunction "OSC2_2") (pintype "passive"))
    )
    (net (code "49") (name "Net-(U7-LEDK)") (class "Default")
      (node (ref "R10") (pin "2") (pinfunction "2_2") (pintype "passive"))
      (node (ref "U7") (pin "2") (pinfunction "LEDK_2") (pintype "passive"))
    )
    (net (code "50") (name "Net-(U10-+)") (class "Default")
      (node (ref "P9") (pin "1") (pinfunction "1_1") (pintype "passive"))
      (node (ref "R7") (pin "2") (pinfunction "2_2") (pintype "passive"))
      (node (ref "U10") (pin "3") (pinfunction "+_3") (pintype "passive"))
    )
    (net (code "51") (name "VBATT") (class "Default")
      (node (ref "U2") (pin "3") (pinfunction "VBAT_3") (pintype "passive"))
      (node (ref "U3") (pin "1") (pinfunction "VIN_1") (pintype "passive"))
      (node (ref "U3") (pin "3") (pinfunction "~{SHDN}_3") (pintype "passive"))
    )
    (net (code "52") (name "unconnected-(BTN1-SHIELD-PadS)") (class "Default")
      (node (ref "BTN1") (pin "S") (pinfunction "SHIELD_S") (pintype "passive"))
    )
    (net (code "53") (name "unconnected-(BTN2-SHIELD-PadS)") (class "Default")
      (node (ref "BTN2") (pin "S") (pinfunction "SHIELD_S") (pintype "passive"))
    )
    (net (code "54") (name "unconnected-(BTN3-SHIELD-PadS)") (class "Default")
      (node (ref "BTN3") (pin "S") (pinfunction "SHIELD_S") (pintype "passive"))
    )
    (net (code "55") (name "unconnected-(J3-KEY-Pad7)") (class "Default")
      (node (ref "J3") (pin "7") (pinfunction "KEY_7") (pintype "passive+no_connect"))
    )
    (net (code "56") (name "unconnected-(J3-TDI-Pad8)") (class "Default")
      (node (ref "J3") (pin "8") (pinfunction "TDI_8") (pintype "passive+no_connect"))
    )
    (net (code "57") (name "unconnected-(RESET1-SHIELD-PadS)") (class "Default")
      (node (ref "RESET1") (pin "S") (pinfunction "SHIELD_S") (pintype "passive"))
    )
    (net (code "58") (name "unconnected-(U3-NC-Pad4)") (class "Default")
      (node (ref "U3") (pin "4") (pinfunction "NC_4") (pintype "passive"))
    )
    (net (code "59") (name "unconnected-(U5-PIO0_0{slash}FC3_SCK{slash}CTIMER0_MAT0{slash}SCT_GPI0{slash}SD1_CARD_INT_N{slash}SECURE_GPIO0_0{slash}ACMP0_A-PadL12)") (class "Default")
      (node (ref "U5") (pin "L12") (pinfunction "PIO0_0/FC3_SCK/CTIMER0_MAT0/SCT_GPI0/SD1_CARD_INT_N/SECURE_GPIO0_0/ACMP0_A_L12") (pintype "passive+no_connect"))
    )
    (net (code "60") (name "unconnected-(U5-PIO0_1{slash}FC3_CTS_SDA_SSEL0{slash}CT_INP0{slash}SCT_GPI1{slash}SD1_CLK{slash}CMP0_OUT{slash}SECURE_GPIO0_1-PadF5)") (class "Default")
      (node (ref "U5") (pin "F5") (pinfunction "PIO0_1/FC3_CTS_SDA_SSEL0/CT_INP0/SCT_GPI1/SD1_CLK/CMP0_OUT/SECURE_GPIO0_1_F5") (pintype "passive+no_connect"))
    )
    (net (code "61") (name "unconnected-(U5-PIO0_4{slash}FC4_SCK{slash}CT_INP12{slash}SCT_GPI4{slash}FC3_CTS_SDA_SSEL0{slash}SECURE_GPIO0_4-PadE7)") (class "Default")
      (node (ref "U5") (pin "E7") (pinfunction "PIO0_4/FC4_SCK/CT_INP12/SCT_GPI4/FC3_CTS_SDA_SSEL0/SECURE_GPIO0_4_E7") (pintype "passive+no_connect"))
    )
    (net (code "62") (name "unconnected-(U5-PIO0_7{slash}FC3_RTS_SCL_SSEL1{slash}SD0_CLK{slash}FC5_SCK{slash}FC1_SCK{slash}SECURE_GPIO0_7-PadG5)") (class "Default")
      (node (ref "U5") (pin "G5") (pinfunction "PIO0_7/FC3_RTS_SCL_SSEL1/SD0_CLK/FC5_SCK/FC1_SCK/SECURE_GPIO0_7_G5") (pintype "passive+no_connect"))
    )
    (net (code "63") (name "unconnected-(U5-PIO0_8{slash}FC3_SSEL3{slash}SD0_CMD{slash}FC5_RXD_SDA_MOSI_DATA{slash}SWO{slash}SECURE_GPIO0_8-PadM2)") (class "Default")
      (node (ref "U5") (pin "M2") (pinfunction "PIO0_8/FC3_SSEL3/SD0_CMD/FC5_RXD_SDA_MOSI_DATA/SWO/SECURE_GPIO0_8_M2") (pintype "passive+no_connect"))
    )
    (net (code "64") (name "unconnected-(U5-PIO0_9{slash}FC3_SSEL2{slash}SD0_POW_EN{slash}FC5_TXD_SCL_MISO_WS{slash}SECURE_GPIO0_9{slash}ACMP0_B-PadL13)") (class "Default")
      (node (ref "U5") (pin "L13") (pinfunction "PIO0_9/FC3_SSEL2/SD0_POW_EN/FC5_TXD_SCL_MISO_WS/SECURE_GPIO0_9/ACMP0_B_L13") (pintype "passive+no_connect"))
    )
    (net (code "65") (name "unconnected-(U5-PIO0_17{slash}FC4_SSEL2{slash}SD0_CARD_DET_N{slash}SCT_GPI7{slash}SCT0_OUT0{slash}SD0_CARD_INT_N{slash}PLU_IN2{slash}SECURE_GPIO0_17-PadG3)") (class "Default")
      (node (ref "U5") (pin "G3") (pinfunction "PIO0_17/FC4_SSEL2/SD0_CARD_DET_N/SCT_GPI7/SCT0_OUT0/SD0_CARD_INT_N/PLU_IN2/SECURE_GPIO0_17_G3") (pintype "passive+no_connect"))
    )
    (net (code "66") (name "unconnected-(U5-PIO0_18{slash}FC4_CTS_SDA_SSEL0{slash}SD0_WR_PRT{slash}CTIMER1_MAT0{slash}SCT0_OUT1{slash}PLU_IN3{slash}SECURE_GPIO0_18{slash}ACMP0_C-PadH9)") (class "Default")
      (node (ref "U5") (pin "H9") (pinfunction "PIO0_18/FC4_CTS_SDA_SSEL0/SD0_WR_PRT/CTIMER1_MAT0/SCT0_OUT1/PLU_IN3/SECURE_GPIO0_18/ACMP0_C_H9") (pintype "passive+no_connect"))
    )
    (net (code "67") (name "unconnected-(U5-PIO0_19{slash}FC4_RTS_SCL_SSEL1{slash}UTICK_CAP0{slash}CTIMER0_MAT2{slash}SCT0_OUT2{slash}FC7_TXD_SCL_MISO_WS{slash}PLU_IN4{slash}SECURE_GPIO0_19-PadE6)") (class "Default")
      (node (ref "U5") (pin "E6") (pinfunction "PIO0_19/FC4_RTS_SCL_SSEL1/UTICK_CAP0/CTIMER0_MAT2/SCT0_OUT2/FC7_TXD_SCL_MISO_WS/PLU_IN4/SECURE_GPIO0_19_E6") (pintype "passive+no_connect"))
    )
    (net (code "68") (name "unconnected-(U5-PIO0_21{slash}FC3_RTS_SCL_SSEL1{slash}UTICK_CAP3{slash}CTIMER3_MAT3{slash}SCT_GPI3{slash}FC7_SCK{slash}PLU_CLKIN{slash}SECURE_GPIO0_21-PadA12)") (class "Default")
      (node (ref "U5") (pin "A12") (pinfunction "PIO0_21/FC3_RTS_SCL_SSEL1/UTICK_CAP3/CTIMER3_MAT3/SCT_GPI3/FC7_SCK/PLU_CLKIN/SECURE_GPIO0_21_A12") (pintype "passive+no_connect"))
    )
    (net (code "69") (name "unconnected-(U5-PIO0_25{slash}FC0_TXD_SCL_MISO_WS{slash}SD0_D1{slash}CT_INP9{slash}SCT_GPI1{slash}SECURE_GPIO0_25-PadA11)") (class "Default")
      (node (ref "U5") (pin "A11") (pinfunction "PIO0_25/FC0_TXD_SCL_MISO_WS/SD0_D1/CT_INP9/SCT_GPI1/SECURE_GPIO0_25_A11") (pintype "passive+no_connect"))
    )
    (net (code "70") (name "unconnected-(U5-PIO0_29{slash}FC0_RXD_SDA_MOSI_DATA{slash}SD1_D[2]{slash}CTIMER2_MAT3{slash}SCT0_OUT8{slash}CMP0_OUT{slash}PLU_OUT2{slash}SEC_PIO0_29-PadH8)") (class "Default")
      (node (ref "U5") (pin "H8") (pinfunction "PIO0_29/FC0_RXD_SDA_MOSI_DATA/SD1_D[2]/CTIMER2_MAT3/SCT0_OUT8/CMP0_OUT/PLU_OUT2/SEC_PIO0_29_H8") (pintype "passive+no_connect"))
    )
    (net (code "71") (name "unconnected-(U5-PIO0_30{slash}FC0_TXD_SCL_MISO_WS{slash}SD1_D[3]{slash}CTIMER0_MAT0{slash}SCT0_OUT9-PadE5)") (class "Default")
      (node (ref "U5") (pin "E5") (pinfunction "PIO0_30/FC0_TXD_SCL_MISO_WS/SD1_D[3]/CTIMER0_MAT0/SCT0_OUT9_E5") (pintype "passive+no_connect"))
    )
    (net (code "72") (name "unconnected-(U5-PIO1_0{slash}FC0_RTS_SCL_SSEL1{slash}SD0_D3{slash}CT_INP2{slash}SCT_GPI4{slash}PLU_OUT3{slash}ADC0_11-PadE1)") (class "Default")
      (node (ref "U5") (pin "E1") (pinfunction "PIO1_0/FC0_RTS_SCL_SSEL1/SD0_D3/CT_INP2/SCT_GPI4/PLU_OUT3/ADC0_11_E1") (pintype "passive+no_connect"))
    )
    (net (code "73") (name "unconnected-(U5-PIO1_6{slash}FC0_TXD_SCL_MISO_WS{slash}SD0_D3{slash}CTIMER2_MAT1{slash}SCT_GPI3-PadH5)") (class "Default")
      (node (ref "U5") (pin "H5") (pinfunction "PIO1_6/FC0_TXD_SCL_MISO_WS/SD0_D3/CTIMER2_MAT1/SCT_GPI3_H5") (pintype "passive+no_connect"))
    )
    (net (code "74") (name "unconnected-(U5-PIO1_7{slash}FC0_RTS_SCL_SSEL1{slash}SD0_D1{slash}CTIMER2_MAT2{slash}SCT_GPI4-PadJ5)") (class "Default")
      (node (ref "U5") (pin "J5") (pinfunction "PIO1_7/FC0_RTS_SCL_SSEL1/SD0_D1/CTIMER2_MAT2/SCT_GPI4_J5") (pintype "passive+no_connect"))
    )
    (net (code "75") (name "unconnected-(U5-PIO1_8{slash}FC0_CTS_SDA_SSEL0{slash}SD0_CLK{slash}SCT0_OUT1{slash}FC4_SSEL2{slash}ADC0_4-PadA6)") (class "Default")
      (node (ref "U5") (pin "A6") (pinfunction "PIO1_8/FC0_CTS_SDA_SSEL0/SD0_CLK/SCT0_OUT1/FC4_SSEL2/ADC0_4_A6") (pintype "passive+no_connect"))
    )
    (net (code "76") (name "unconnected-(U5-PIO1_10{slash}FC1_RXD_SDA_MOSI_DATA{slash}CTIMER1_MAT0{slash}SCT0_OUT3-PadJ7)") (class "Default")
      (node (ref "U5") (pin "J7") (pinfunction "PIO1_10/FC1_RXD_SDA_MOSI_DATA/CTIMER1_MAT0/SCT0_OUT3_J7") (pintype "passive+no_connect"))
    )
    (net (code "77") (name "unconnected-(U5-PIO1_11{slash}FC1_TXD_SCL_MISO_WS{slash}CT_INP5{slash}USB0_VBUS-PadG6)") (class "Default")
      (node (ref "U5") (pin "G6") (pinfunction "PIO1_11/FC1_TXD_SCL_MISO_WS/CT_INP5/USB0_VBUS_G6") (pintype "passive+no_connect"))
    )
    (net (code "78") (name "unconnected-(U5-PIO1_13{slash}FC6_RXD_SDA_MOSI_DATA{slash}CT_INP6{slash}USB0_OVERCURRENTN{slash}USB0_FRAME{slash}SD0_CARD_DET_N-PadB3)") (class "Default")
      (node (ref "U5") (pin "B3") (pinfunction "PIO1_13/FC6_RXD_SDA_MOSI_DATA/CT_INP6/USB0_OVERCURRENTN/USB0_FRAME/SD0_CARD_DET_N_B3") (pintype "passive+no_connect"))
    )
    (net (code "79") (name "unconnected-(U5-PIO1_14{slash}UTICK_CAP2{slash}CTIMER1_MAT2{slash}FC5_CTS_SDA_SSEL0{slash}USB0_LEDN{slash}SD1_CMD{slash}ACMP0_D-PadL7)") (class "Default")
      (node (ref "U5") (pin "L7") (pinfunction "PIO1_14/UTICK_CAP2/CTIMER1_MAT2/FC5_CTS_SDA_SSEL0/USB0_LEDN/SD1_CMD/ACMP0_D_L7") (pintype "passive+no_connect"))
    )
    (net (code "80") (name "unconnected-(U5-PIO1_15{slash}UTICK_CAP3{slash}CT_INP7{slash}FC5_RTS_SCL_SSEL1{slash}FC4_RTS_SCL_SSEL1{slash}SD1_D2-PadB6)") (class "Default")
      (node (ref "U5") (pin "B6") (pinfunction "PIO1_15/UTICK_CAP3/CT_INP7/FC5_RTS_SCL_SSEL1/FC4_RTS_SCL_SSEL1/SD1_D2_B6") (pintype "passive+no_connect"))
    )
    (net (code "81") (name "unconnected-(U5-PIO1_16{slash}FC6_TXD_SCL_MISO_WS{slash}CTIMER1_MAT3{slash}SD0_CMD-PadC7)") (class "Default")
      (node (ref "U5") (pin "C7") (pinfunction "PIO1_16/FC6_TXD_SCL_MISO_WS/CTIMER1_MAT3/SD0_CMD_C7") (pintype "passive+no_connect"))
    )
    (net (code "82") (name "unconnected-(U5-PIO1_17{slash}FC6_RTS_SCL_SSEL1{slash}SCT0_OUT4{slash}SD1_CARD_INT_N{slash}SD1_CARD_DET_N-PadJ9)") (class "Default")
      (node (ref "U5") (pin "J9") (pinfunction "PIO1_17/FC6_RTS_SCL_SSEL1/SCT0_OUT4/SD1_CARD_INT_N/SD1_CARD_DET_N_J9") (pintype "passive+no_connect"))
    )
    (net (code "83") (name "unconnected-(U5-PIO1_18{slash}SD1_POW_EN{slash}SCT0_OUT5{slash}PLU_OUT0-PadG9)") (class "Default")
      (node (ref "U5") (pin "G9") (pinfunction "PIO1_18/SD1_POW_EN/SCT0_OUT5/PLU_OUT0_G9") (pintype "passive+no_connect"))
    )
    (net (code "84") (name "unconnected-(U5-PIO1_20{slash}FC7_RTS_SCL_SSEL1{slash}CT_INP14{slash}FC4_TXD_SCL_MISO_WS{slash}PLU_OUT2-PadC2)") (class "Default")
      (node (ref "U5") (pin "C2") (pinfunction "PIO1_20/FC7_RTS_SCL_SSEL1/CT_INP14/FC4_TXD_SCL_MISO_WS/PLU_OUT2_C2") (pintype "passive+no_connect"))
    )
    (net (code "85") (name "unconnected-(U5-PIO1_21{slash}FC7_CTS_SDA_SSEL0{slash}CTIMER3_MAT2{slash}FC4_RXD_SDA_MOSI_DATA{slash}PLU_OUT3-PadM7)") (class "Default")
      (node (ref "U5") (pin "M7") (pinfunction "PIO1_21/FC7_CTS_SDA_SSEL0/CTIMER3_MAT2/FC4_RXD_SDA_MOSI_DATA/PLU_OUT3_M7") (pintype "passive+no_connect"))
    )
    (net (code "86") (name "unconnected-(U5-PIO1_23{slash}FC2_SCK{slash}SCT0_OUT0{slash}SD1_D3{slash}FC3_SSEL2{slash}PLU_OUT5-PadJ8)") (class "Default")
      (node (ref "U5") (pin "J8") (pinfunction "PIO1_23/FC2_SCK/SCT0_OUT0/SD1_D3/FC3_SSEL2/PLU_OUT5_J8") (pintype "passive+no_connect"))
    )
    (net (code "87") (name "unconnected-(U5-PIO1_24{slash}FC2_RXD_SDA_MOSI_DATA{slash}SCT0_OUT1{slash}SD1_D1{slash}FC3_SSEL3{slash}PLU_OUT6-PadF6)") (class "Default")
      (node (ref "U5") (pin "F6") (pinfunction "PIO1_24/FC2_RXD_SDA_MOSI_DATA/SCT0_OUT1/SD1_D1/FC3_SSEL3/PLU_OUT6_F6") (pintype "passive+no_connect"))
    )
    (net (code "88") (name "unconnected-(U5-PIO1_25{slash}FC2_TXD_SCL_MISO_WS{slash}SCT0_OUT2{slash}SD1_D0{slash}UTICK_CAP0{slash}PLU_CLKIN-PadB8)") (class "Default")
      (node (ref "U5") (pin "B8") (pinfunction "PIO1_25/FC2_TXD_SCL_MISO_WS/SCT0_OUT2/SD1_D0/UTICK_CAP0/PLU_CLKIN_B8") (pintype "passive+no_connect"))
    )
    (net (code "89") (name "unconnected-(U5-PIO1_27{slash}FC2_RTS_SCL_SSEL1{slash}SD0_D4{slash}CTIMER0_MAT3{slash}CLKOUT{slash}PLU_IN4-PadE8)") (class "Default")
      (node (ref "U5") (pin "E8") (pinfunction "PIO1_27/FC2_RTS_SCL_SSEL1/SD0_D4/CTIMER0_MAT3/CLKOUT/PLU_IN4_E8") (pintype "passive+no_connect"))
    )
    (net (code "90") (name "unconnected-(U5-PIO1_28{slash}FC7_SCK{slash}SD0_D5{slash}CT_INP2{slash}PLU_IN3-PadA8)") (class "Default")
      (node (ref "U5") (pin "A8") (pinfunction "PIO1_28/FC7_SCK/SD0_D5/CT_INP2/PLU_IN3_A8") (pintype "passive+no_connect"))
    )
    (net (code "91") (name "unconnected-(U5-PIO1_29{slash}FC7_RXD_SDA_MOSI_DATA{slash}SD0_D6{slash}SCT_GPI6{slash}USB1_PORTPWRN{slash}USB1_FRAME{slash}PLU_IN2-PadG8)") (class "Default")
      (node (ref "U5") (pin "G8") (pinfunction "PIO1_29/FC7_RXD_SDA_MOSI_DATA/SD0_D6/SCT_GPI6/USB1_PORTPWRN/USB1_FRAME/PLU_IN2_G8") (pintype "passive+no_connect"))
    )
    (net (code "92") (name "unconnected-(U5-PIO1_30{slash}FC7_TXD_SCL_MISO_WS{slash}SD0_D7{slash}SCT_GPI7{slash}USB1_OVERCURRENTN{slash}USB1_LEDN{slash}PLU_IN1-PadF9)") (class "Default")
      (node (ref "U5") (pin "F9") (pinfunction "PIO1_30/FC7_TXD_SCL_MISO_WS/SD0_D7/SCT_GPI7/USB1_OVERCURRENTN/USB1_LEDN/PLU_IN1_F9") (pintype "passive+no_connect"))
    )
    (net (code "93") (name "unconnected-(U5-PIO1_31{slash}MCLK{slash}SD1_CLK{slash}CTIMER0_MAT2{slash}SCT0_OUT6{slash}PLU_IN0-PadH6)") (class "Default")
      (node (ref "U5") (pin "H6") (pinfunction "PIO1_31/MCLK/SD1_CLK/CTIMER0_MAT2/SCT0_OUT6/PLU_IN0_H6") (pintype "passive+no_connect"))
    )
    (net (code "94") (name "unconnected-(U5-USB1_3V3-PadN7)") (class "Default")
      (node (ref "U5") (pin "N7") (pinfunction "USB1_3V3_N7") (pintype "passive+no_connect"))
    )
    (net (code "95") (name "unconnected-(U5-USB1_DM-PadN6)") (class "Default")
      (node (ref "U5") (pin "N6") (pinfunction "USB1_DM_N6") (pintype "passive+no_connect"))
    )
    (net (code "96") (name "unconnected-(U5-USB1_DP-PadM6)") (class "Default")
      (node (ref "U5") (pin "M6") (pinfunction "USB1_DP_M6") (pintype "passive+no_connect"))
    )
    (net (code "97") (name "unconnected-(U5-USB1_VBUS-PadN8)") (class "Default")
      (node (ref "U5") (pin "N8") (pinfunction "USB1_VBUS_N8") (pintype "passive+no_connect"))
    )
    (net (code "98") (name "unconnected-(U5-XTAL32K_N-PadJ12)") (class "Default")
      (node (ref "U5") (pin "J12") (pinfunction "XTAL32K_N_J12") (pintype "passive"))
    )
    (net (code "99") (name "unconnected-(U5-XTAL32K_P-PadJ13)") (class "Default")
      (node (ref "U5") (pin "J13") (pinfunction "XTAL32K_P_J13") (pintype "passive"))
    )
  )
)
